# TFT.net
KiCad netlist of a schematic drawn in Altium Designer
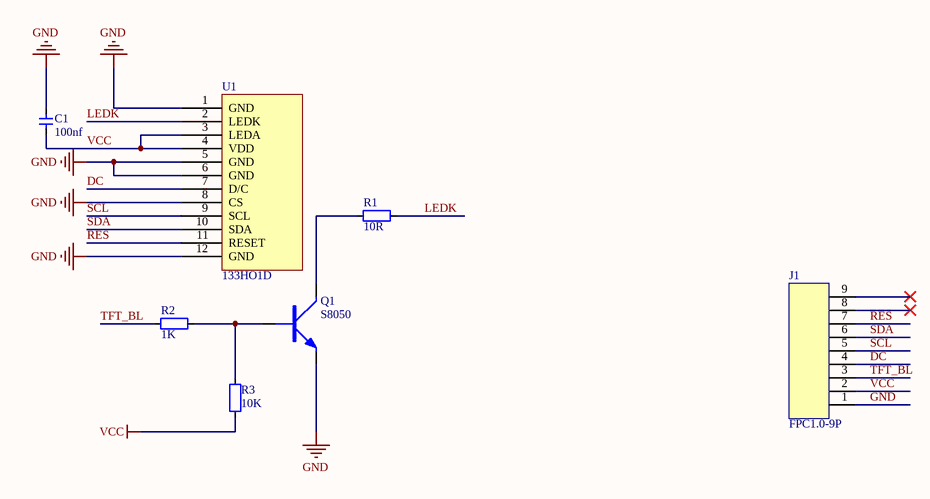
[diagram p0: TFT.SchDoc]

(export (version "E")
  (design (tool "Eeschema 10.0.6"))
  (components
    (comp (ref "C1")
      (value "100nf")
      (footprint "0603C")
      (description "无极性电容")
      (libsource (lib "电容") (part "CAP"))
    )
    (comp (ref "J1")
      (value "FPC1.0-9P")
      (footprint "FPC1.0-9P")
      (description "贴片")
      (libsource (lib "FPC") (part "FPC1.0-9P"))
    )
    (comp (ref "Q1")
      (value "S8050")
      (footprint "SOT-23")
      (description "NPN三极管")
      (libsource (lib "三极管") (part "NPN"))
    )
    (comp (ref "R1") (value "10R") (footprint "0603R") (libsource (lib "电阻") (part "RES")))
    (comp (ref "R2") (value "1K") (footprint "0603R") (libsource (lib "电阻") (part "RES")))
    (comp (ref "R3") (value "10K") (footprint "0603R") (libsource (lib "") (part "RES_1")))
    (comp (ref "U1")
      (value "133HO1D")
      (footprint "LCD-240X240-NOHOLE")
      (description "1.3 TFT IPS")
      (libsource (lib "LCD") (part "133HO1D"))
    )
  )
  (nets
    (net (code "1") (name "/DC") (class "Default")
      (node (ref "J1") (pin "4") (pinfunction "4_4") (pintype "passive"))
      (node (ref "U1") (pin "7") (pinfunction "D/C_7") (pintype "passive"))
    )
    (net (code "2") (name "/LEDK") (class "Default")
      (node (ref "R1") (pin "2") (pinfunction "2_2") (pintype "passive"))
      (node (ref "U1") (pin "2") (pinfunction "LEDK_2") (pintype "passive"))
    )
    (net (code "3") (name "/RES") (class "Default")
      (node (ref "J1") (pin "7") (pinfunction "7_7") (pintype "passive"))
      (node (ref "U1") (pin "11") (pinfunction "RESET_11") (pintype "passive"))
    )
    (net (code "4") (name "/SCL") (class "Default")
      (node (ref "J1") (pin "5") (pinfunction "5_5") (pintype "passive"))
      (node (ref "U1") (pin "9") (pinfunction "SCL_9") (pintype "passive"))
    )
    (net (code "5") (name "/SDA") (class "Default")
      (node (ref "J1") (pin "6") (pinfunction "6_6") (pintype "passive"))
      (node (ref "U1") (pin "10") (pinfunction "SDA_10") (pintype "passive"))
    )
    (net (code "6") (name "/TFT_BL") (class "Default")
      (node (ref "J1") (pin "3") (pinfunction "3_3") (pintype "passive"))
      (node (ref "R2") (pin "1") (pinfunction "1_1") (pintype "passive"))
    )
    (net (code "7") (name "GND") (class "Default")
      (node (ref "C1") (pin "2") (pinfunction "2_2") (pintype "passive"))
      (node (ref "J1") (pin "1") (pinfunction "1_1") (pintype "passive"))
      (node (ref "Q1") (pin "E") (pinfunction "E_E") (pintype "passive"))
      (node (ref "U1") (pin "1") (pinfunction "GND_1") (pintype "passive"))
      (node (ref "U1") (pin "12") (pinfunction "GND_12") (pintype "passive"))
      (node (ref "U1") (pin "5") (pinfunction "GND_5") (pintype "passive"))
      (node (ref "U1") (pin "6") (pinfunction "GND_6") (pintype "passive"))
      (node (ref "U1") (pin "8") (pinfunction "CS_8") (pintype "passive"))
    )
    (net (code "8") (name "Net-(Q1-PadB)") (class "Default")
      (node (ref "Q1") (pin "B") (pinfunction "B_B") (pintype "passive"))
      (node (ref "R2") (pin "2") (pinfunction "2_2") (pintype "passive"))
      (node (ref "R3") (pin "2") (pinfunction "2_2") (pintype "passive"))
    )
    (net (code "9") (name "Net-(Q1-PadC)") (class "Default")
      (node (ref "Q1") (pin "C") (pinfunction "C_C") (pintype "passive"))
      (node (ref "R1") (pin "1") (pinfunction "1_1") (pintype "passive"))
    )
    (net (code "10") (name "VCC") (class "Default")
      (node (ref "C1") (pin "1") (pinfunction "1_1") (pintype "passive"))
      (node (ref "J1") (pin "2") (pinfunction "2_2") (pintype "passive"))
      (node (ref "R3") (pin "1") (pinfunction "1_1") (pintype "passive"))
      (node (ref "U1") (pin "3") (pinfunction "LEDA_3") (pintype "passive"))
      (node (ref "U1") (pin "4") (pinfunction "VDD_4") (pintype "passive"))
    )
    (net (code "11") (name "unconnected-(J1-Pad8)") (class "Default")
      (node (ref "J1") (pin "8") (pinfunction "8_8") (pintype "passive+no_connect"))
    )
    (net (code "12") (name "unconnected-(J1-Pad9)") (class "Default")
      (node (ref "J1") (pin "9") (pinfunction "9_9") (pintype "passive+no_connect"))
    )
  )
)
